# drv8837c-breakout.net
KiCad netlist of a schematic drawn in EAGLE
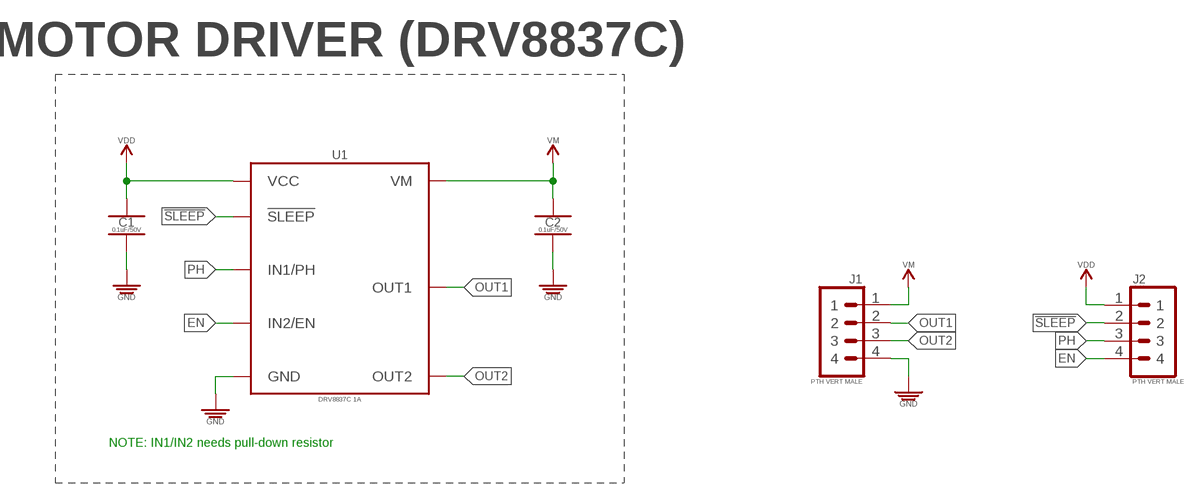
[diagram p0: schematic, sheet 1]

(export (version "E")
  (design (tool "Eeschema 10.0.6"))
  (components
    (comp (ref "C1")
      (value "0.1uF/50V")
      (footprint "eagle-import:CAPC1005X55_SMD-0402")
      (fields (field (name "MFR") "TDK Corporation") (field (name "MPN") "C1005X7R1H104K050BE"))
      (libsource (lib "eagle-import") (part "0.1UF_SMD-0402_50V-10%"))
    )
    (comp (ref "C2")
      (value "0.1uF/50V")
      (footprint "eagle-import:CAPC1005X55_SMD-0402")
      (fields (field (name "MFR") "TDK Corporation") (field (name "MPN") "C1005X7R1H104K050BE"))
      (libsource (lib "eagle-import") (part "0.1UF_SMD-0402_50V-10%"))
    )
    (comp (ref "J1")
      (value "PTH VERT MALE")
      (footprint "eagle-import:HDRV4W64P254_1X4_1016X254X838B")
      (fields (field (name "MFR") "Sullins Connector Solutions") (field (name "MPN") "PEC04SAAN"))
      (libsource (lib "eagle-import") (part "1X04_PTH_VERT_MALE_2.54MM"))
    )
    (comp (ref "J2")
      (value "PTH VERT MALE")
      (footprint "eagle-import:HDRV4W64P254_1X4_1016X254X838B")
      (fields (field (name "MFR") "Sullins Connector Solutions") (field (name "MPN") "PEC04SAAN"))
      (libsource (lib "eagle-import") (part "1X04_PTH_VERT_MALE_2.54MM"))
    )
    (comp (ref "U1")
      (value "DRV8837C 1A")
      (footprint "eagle-import:WSON-8-PPAD")
      (fields (field (name "MFR") "Texas Instruments") (field (name "MPN") "DRV8837CDSGT"))
      (libsource (lib "eagle-import") (part "DRV883X_H-BRIDGE_DRV8837C_1A"))
    )
  )
  (nets
    (net (code "1") (name "/~{SLEEP}") (class "Default")
      (node (ref "J2") (pin "2") (pinfunction "2_2") (pintype "passive"))
      (node (ref "U1") (pin "7") (pinfunction "~{SLEEP}_7") (pintype "passive"))
    )
    (net (code "2") (name "EN") (class "Default")
      (node (ref "J2") (pin "4") (pinfunction "4_4") (pintype "passive"))
      (node (ref "U1") (pin "5") (pinfunction "IN2/EN_5") (pintype "input"))
    )
    (net (code "3") (name "GND") (class "Default")
      (node (ref "C1") (pin "2") (pinfunction "2_2") (pintype "passive"))
      (node (ref "C2") (pin "2") (pinfunction "2_2") (pintype "passive"))
      (node (ref "J1") (pin "4") (pinfunction "4_4") (pintype "passive"))
      (node (ref "U1") (pin "4") (pinfunction "GND_4") (pintype "passive"))
      (node (ref "U1") (pin "GND") (pinfunction "GND_GND") (pintype "passive"))
      (node (ref "U1") (pin "P$1") (pinfunction "GND_P$1") (pintype "passive"))
      (node (ref "U1") (pin "P$2") (pinfunction "GND_P$2") (pintype "passive"))
    )
    (net (code "4") (name "OUT1") (class "Default")
      (node (ref "J1") (pin "2") (pinfunction "2_2") (pintype "passive"))
      (node (ref "U1") (pin "2") (pinfunction "OUT1_2") (pintype "passive"))
    )
    (net (code "5") (name "OUT2") (class "Default")
      (node (ref "J1") (pin "3") (pinfunction "3_3") (pintype "passive"))
      (node (ref "U1") (pin "3") (pinfunction "OUT2_3") (pintype "passive"))
    )
    (net (code "6") (name "PH") (class "Default")
      (node (ref "J2") (pin "3") (pinfunction "3_3") (pintype "passive"))
      (node (ref "U1") (pin "6") (pinfunction "IN1/PH_6") (pintype "input"))
    )
    (net (code "7") (name "VDD") (class "Default")
      (node (ref "C1") (pin "1") (pinfunction "1_1") (pintype "passive"))
      (node (ref "J2") (pin "1") (pinfunction "1_1") (pintype "passive"))
      (node (ref "U1") (pin "8") (pinfunction "VCC_8") (pintype "passive"))
    )
    (net (code "8") (name "VM") (class "Default")
      (node (ref "C2") (pin "1") (pinfunction "1_1") (pintype "passive"))
      (node (ref "J1") (pin "1") (pinfunction "1_1") (pintype "passive"))
      (node (ref "U1") (pin "1") (pinfunction "VM_1") (pintype "passive"))
    )
  )
)
